# CH32F203RBT6-R1.net
KiCad netlist of a schematic drawn in Altium Designer
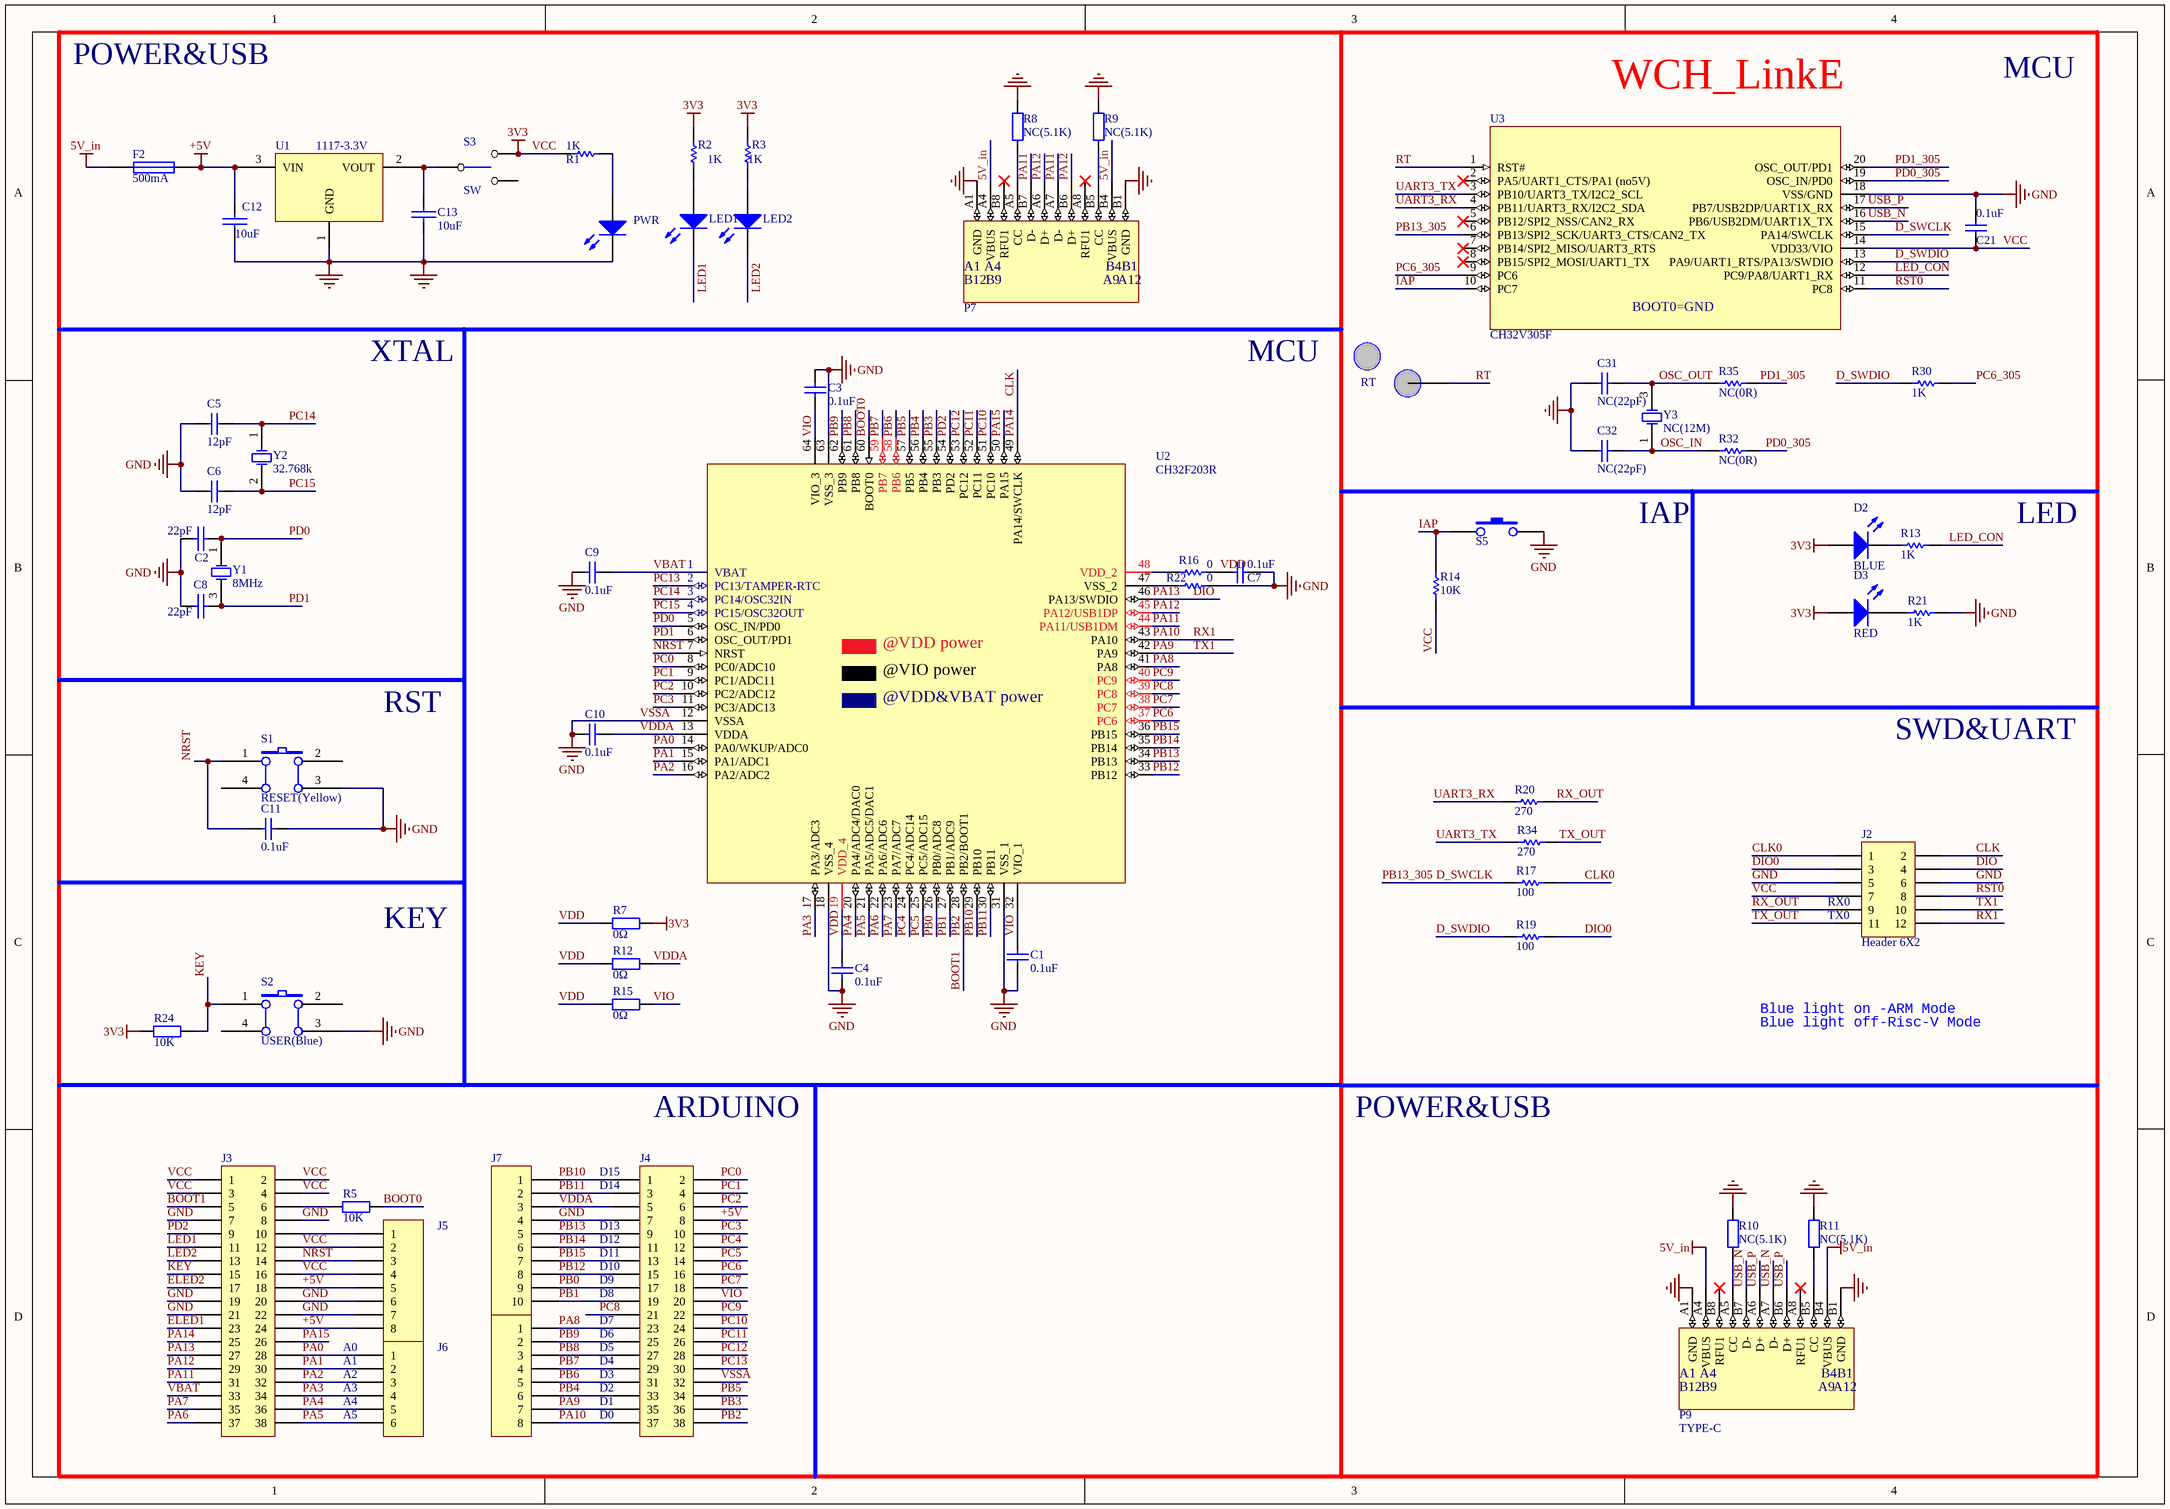
[diagram p0: CH32F203RBT6-R1.SchDoc]

(export (version "E")
  (design (tool "Eeschema 10.0.6"))
  (components
    (comp (ref "C1")
      (value "0.1uF")
      (footprint "0603_C")
      (description "Capacitor")
      (libsource (lib "Miscellaneous Devices") (part "Cap"))
    )
    (comp (ref "C2")
      (value "22pF")
      (footprint "0603_C")
      (description "Capacitor")
      (libsource (lib "*") (part "CAP"))
    )
    (comp (ref "C3")
      (value "0.1uF")
      (footprint "0603_C")
      (description "Capacitor")
      (libsource (lib "Miscellaneous Devices") (part "Cap"))
    )
    (comp (ref "C4")
      (value "0.1uF")
      (footprint "0603_C")
      (description "Capacitor")
      (libsource (lib "Miscellaneous Devices") (part "Cap"))
    )
    (comp (ref "C5")
      (value "12pF")
      (footprint "0603_C")
      (description "Capacitor")
      (libsource (lib "Miscellaneous Devices") (part "Cap"))
    )
    (comp (ref "C6")
      (value "12pF")
      (footprint "0603_C")
      (description "Capacitor")
      (libsource (lib "Miscellaneous Devices") (part "Cap"))
    )
    (comp (ref "C7")
      (value "0.1uF")
      (footprint "0603_C")
      (description "Capacitor")
      (libsource (lib "Miscellaneous Devices") (part "Cap"))
    )
    (comp (ref "C8")
      (value "22pF")
      (footprint "0603_C")
      (description "Capacitor")
      (libsource (lib "*") (part "CAP"))
    )
    (comp (ref "C9")
      (value "0.1uF")
      (footprint "0603_C")
      (description "Capacitor")
      (libsource (lib "Miscellaneous Devices") (part "Cap"))
    )
    (comp (ref "C10")
      (value "0.1uF")
      (footprint "0603_C")
      (description "Capacitor")
      (libsource (lib "Miscellaneous Devices") (part "Cap"))
    )
    (comp (ref "C11")
      (value "0.1uF")
      (footprint "0603_C")
      (description "Capacitor")
      (libsource (lib "Miscellaneous Devices") (part "Cap"))
    )
    (comp (ref "C12")
      (value "10uF")
      (footprint "3216_C")
      (description "Capacitor")
      (libsource (lib "*") (part "CAP"))
    )
    (comp (ref "C13")
      (value "10uF")
      (footprint "3216_C")
      (description "Capacitor")
      (libsource (lib "*") (part "CAP"))
    )
    (comp (ref "C21")
      (value "0.1uF")
      (footprint "0603_C")
      (description "Capacitor")
      (libsource (lib "Miscellaneous Devices") (part "Cap"))
    )
    (comp (ref "C31")
      (value "NC(22pF)")
      (footprint "0603_C")
      (description "Capacitor")
      (fields (field (name "PUBLISHER") "Altium Limited"))
      (libsource (lib "*") (part "Cap"))
    )
    (comp (ref "C32")
      (value "NC(22pF)")
      (footprint "0603_C")
      (description "Capacitor")
      (fields (field (name "PUBLISHER") "Altium Limited"))
      (libsource (lib "*") (part "Cap"))
    )
    (comp (ref "D2")
      (value "BLUE")
      (footprint "0603+")
      (description "Typical RED, GREEN, YELLOW, AMBER GaAs LED")
      (fields (field (name "PUBLISHER") "Altium Limited"))
      (libsource (lib "MYLIB") (part "D0603"))
    )
    (comp (ref "D3")
      (value "RED")
      (footprint "0603+")
      (description "Typical RED, GREEN, YELLOW, AMBER GaAs LED")
      (fields (field (name "PUBLISHER") "Altium Limited"))
      (libsource (lib "MYLIB") (part "D0603"))
    )
    (comp (ref "F2")
      (value "500mA")
      (footprint "0805")
      (description "Fuse")
      (libsource (lib "*") (part "FUSE1"))
    )
    (comp (ref "J2")
      (value "Header 6X2")
      (footprint "IDC12-2.54mm")
      (description "Header, 6-Pin, Dual row")
      (fields (field (name "PUBLISHER") "Altium Limited"))
      (libsource (lib "Miscellaneous Connectors") (part "Header 6X2"))
    )
    (comp (ref "J3")
      (value "Header 19X2")
      (footprint "IDC38-2.54mm")
      (description "Header, 19-Pin, Dual row")
      (fields (field (name "PUBLISHER") "Altium Limited"))
      (libsource (lib "Miscellaneous Connectors") (part "Header 19X2"))
    )
    (comp (ref "J4")
      (value "Header 19X2")
      (footprint "IDC38-2.54mm")
      (description "Header, 19-Pin, Dual row")
      (fields (field (name "PUBLISHER") "Altium Limited"))
      (libsource (lib "Miscellaneous Connectors") (part "Header 19X2"))
    )
    (comp (ref "J5")
      (value "Header 8")
      (footprint "SIP8-2.54mm")
      (description "Header, 8-Pin")
      (fields (field (name "PUBLISHER") "Altium Limited"))
      (libsource (lib "Miscellaneous Connectors") (part "Header 8"))
    )
    (comp (ref "J6")
      (value "Header 6")
      (footprint "SIP6-2.54MM")
      (description "Header, 6-Pin")
      (fields (field (name "PUBLISHER") "Altium Limited"))
      (libsource (lib "Miscellaneous Connectors") (part "Header 6"))
    )
    (comp (ref "J7")
      (value "Header 10")
      (footprint "SIP10-2.54mm")
      (description "Header, 10-Pin")
      (fields (field (name "PUBLISHER") "Altium Limited"))
      (libsource (lib "Miscellaneous Connectors") (part "Header 10"))
    )
    (comp (ref "J8")
      (value "Header 8")
      (footprint "SIP8-2.54mm")
      (description "Header, 8-Pin")
      (fields (field (name "PUBLISHER") "Altium Limited"))
      (libsource (lib "") (part "Header 8_1"))
    )
    (comp (ref "LED1")
      (value "LED1   blue")
      (footprint "0603+")
      (description "Typical INFRARED GaAs LED")
      (fields (field (name "PUBLISHER") "Altium Limited"))
      (libsource (lib "Miscellaneous Devices") (part "LED0"))
    )
    (comp (ref "LED2")
      (value "LED2  blue")
      (footprint "0603+")
      (description "Typical INFRARED GaAs LED")
      (fields (field (name "PUBLISHER") "Altium Limited"))
      (libsource (lib "Miscellaneous Devices") (part "LED0"))
    )
    (comp (ref "P7")
      (value "TYPE-C")
      (footprint "TYPE-C-Receptacle-2.0")
      (libsource (lib "*") (part "TYPE-C1"))
    )
    (comp (ref "P9")
      (value "TYPE-C")
      (footprint "TYPE-C-Receptacle-2.0")
      (libsource (lib "*") (part "TYPE-C1"))
    )
    (comp (ref "PWR")
      (value "POWER  red")
      (footprint "0603+")
      (description "Typical INFRARED GaAs LED")
      (fields (field (name "PUBLISHER") "Altium Limited"))
      (libsource (lib "Miscellaneous Devices") (part "LED0"))
    )
    (comp (ref "R1")
      (value "1K")
      (footprint "0603")
      (description "Semiconductor Resistor")
      (libsource (lib "Miscellaneous Devices") (part "Res Semi"))
    )
    (comp (ref "R2")
      (value "1K")
      (footprint "0603")
      (description "Semiconductor Resistor")
      (libsource (lib "Miscellaneous Devices") (part "Res Semi"))
    )
    (comp (ref "R3")
      (value "1K")
      (footprint "0603")
      (description "Semiconductor Resistor")
      (libsource (lib "Miscellaneous Devices") (part "Res Semi"))
    )
    (comp (ref "R5")
      (value "10K")
      (footprint "0603")
      (description "Resistor")
      (libsource (lib "") (part "Res2_2"))
    )
    (comp (ref "R7")
      (value "0Ω")
      (footprint "0603")
      (description "Resistor")
      (libsource (lib "Miscellaneous Devices") (part "Res2"))
    )
    (comp (ref "R8")
      (value "NC(5.1K)")
      (footprint "0603")
      (description "Resistor")
      (libsource (lib "") (part "Res2_1"))
    )
    (comp (ref "R9")
      (value "NC(5.1K)")
      (footprint "0603")
      (description "Resistor")
      (libsource (lib "") (part "Res2_1"))
    )
    (comp (ref "R10")
      (value "NC(5.1K)")
      (footprint "0603")
      (description "Resistor")
      (libsource (lib "") (part "Res2_3"))
    )
    (comp (ref "R11")
      (value "NC(5.1K)")
      (footprint "0603")
      (description "Resistor")
      (libsource (lib "") (part "Res2_3"))
    )
    (comp (ref "R12")
      (value "0Ω")
      (footprint "0603")
      (description "Resistor")
      (libsource (lib "Miscellaneous Devices") (part "Res2"))
    )
    (comp (ref "R13")
      (value "1K")
      (footprint "0603")
      (description "Resistor")
      (fields (field (name "PUBLISHER") "Altium Limited"))
      (libsource (lib "MYLIB") (part "0603-1"))
    )
    (comp (ref "R14")
      (value "10K")
      (footprint "0603")
      (description "Resistor")
      (fields (field (name "PUBLISHER") "Altium Limited"))
      (libsource (lib "MYLIB") (part "0603-1"))
    )
    (comp (ref "R15")
      (value "0Ω")
      (footprint "0603")
      (description "Resistor")
      (libsource (lib "Miscellaneous Devices") (part "Res2"))
    )
    (comp (ref "R16")
      (value "0")
      (footprint "0603")
      (description "Resistor")
      (fields (field (name "PUBLISHER") "Altium Limited"))
      (libsource (lib "MYLIB") (part "0603-1"))
    )
    (comp (ref "R17")
      (value "100")
      (footprint "0603")
      (description "Resistor")
      (fields (field (name "PUBLISHER") "Altium Limited"))
      (libsource (lib "MYLIB") (part "0603-1"))
    )
    (comp (ref "R19")
      (value "100")
      (footprint "0603")
      (description "Resistor")
      (fields (field (name "PUBLISHER") "Altium Limited"))
      (libsource (lib "MYLIB") (part "0603-1"))
    )
    (comp (ref "R20")
      (value "270")
      (footprint "0603")
      (description "Resistor")
      (fields (field (name "PUBLISHER") "Altium Limited"))
      (libsource (lib "MYLIB") (part "0603-1"))
    )
    (comp (ref "R21")
      (value "1K")
      (footprint "0603")
      (description "Resistor")
      (fields (field (name "PUBLISHER") "Altium Limited"))
      (libsource (lib "MYLIB") (part "0603-1"))
    )
    (comp (ref "R22")
      (value "0")
      (footprint "0603")
      (description "Resistor")
      (fields (field (name "PUBLISHER") "Altium Limited"))
      (libsource (lib "MYLIB") (part "0603-1"))
    )
    (comp (ref "R24")
      (value "10K")
      (footprint "0603")
      (description "Resistor")
      (libsource (lib "Miscellaneous Devices") (part "Res2"))
    )
    (comp (ref "R30")
      (value "1K")
      (footprint "0603")
      (description "Resistor")
      (fields (field (name "PUBLISHER") "Altium Limited"))
      (libsource (lib "MYLIB") (part "0603-1"))
    )
    (comp (ref "R32")
      (value "NC(0R)")
      (footprint "0603")
      (description "Resistor")
      (fields (field (name "PUBLISHER") "Altium Limited"))
      (libsource (lib "MYLIB") (part "0603-1"))
    )
    (comp (ref "R34")
      (value "270")
      (footprint "0603")
      (description "Resistor")
      (fields (field (name "PUBLISHER") "Altium Limited"))
      (libsource (lib "MYLIB") (part "0603-1"))
    )
    (comp (ref "R35")
      (value "NC(0R)")
      (footprint "0603")
      (description "Resistor")
      (fields (field (name "PUBLISHER") "Altium Limited"))
      (libsource (lib "MYLIB") (part "0603-1"))
    )
    (comp (ref "RT")
      (value "Testpoint")
      (footprint "TESTPOINT1")
      (description "测试点")
      (libsource (lib "wch_sch_others") (part "Testpoint"))
    )
    (comp (ref "S1")
      (value "RESET(Yellow)")
      (footprint "KEYX")
      (description "SE PUSHBUTTON")
      (libsource (lib "Documents") (part "SW PUSHBUTTON"))
    )
    (comp (ref "S2")
      (value "USER(Blue)")
      (footprint "KEYX")
      (description "SE PUSHBUTTON")
      (libsource (lib "Documents") (part "SW PUSHBUTTON"))
    )
    (comp (ref "S3") (value "SW") (footprint "SW1") (libsource (lib "MYSCH") (part "SW")))
    (comp (ref "S5") (value "KEY") (footprint "贴片按键") (libsource (lib "*") (part "KEY")))
    (comp (ref "U1")
      (value "1117-3.3V")
      (footprint "SOT-223")
      (libsource (lib "wch_sch_others") (part "1117-3.3V"))
    )
    (comp (ref "U2")
      (value "CH32F203R")
      (footprint "LQFP64M_10x10")
      (description "ARM M3 HD-MCU, 144MHz, 8*UART, 10*Timer, 4*OPA")
      (libsource (lib "CHXXX") (part "CH32F203R"))
    )
    (comp (ref "U3")
      (value "CH32V305F")
      (footprint "TSSOP20")
      (description "RISC-V FPU HD-MCU, 144MHz, USB_480M, CAN, UART*2, SPI")
      (libsource (lib "CHXXX") (part "CH32V305F"))
    )
    (comp (ref "Y1")
      (value "8MHz")
      (footprint "XT3225")
      (description "Crystal Oscillator")
      (fields (field (name "PUBLISHER") "Altium Limited"))
      (libsource (lib "*") (part "XTAL"))
    )
    (comp (ref "Y2")
      (value "32.768k")
      (footprint "FC-135")
      (description "Crystal Oscillator")
      (fields (field (name "PUBLISHER") "Altium Limited"))
      (libsource (lib "Miscellaneous Devices") (part "XTAL"))
    )
    (comp (ref "Y3")
      (value "NC(12M)")
      (footprint "XT3225")
      (description "Crystal Oscillator")
      (libsource (lib "*") (part "XTAL"))
    )
  )
  (nets
    (net (code "1") (name "+5V") (class "Default")
      (node (ref "C12") (pin "1") (pinfunction "1_1") (pintype "passive"))
      (node (ref "F2") (pin "2") (pinfunction "2_2") (pintype "passive"))
      (node (ref "J3") (pin "18") (pinfunction "18_18") (pintype "passive"))
      (node (ref "J3") (pin "24") (pinfunction "24_24") (pintype "passive"))
      (node (ref "J4") (pin "8") (pinfunction "8_8") (pintype "passive"))
      (node (ref "J5") (pin "5") (pinfunction "5_5") (pintype "passive"))
      (node (ref "J5") (pin "8") (pinfunction "8_8") (pintype "passive"))
      (node (ref "U1") (pin "3") (pinfunction "VIN_3") (pintype "passive"))
    )
    (net (code "2") (name "/BOOT0") (class "Default")
      (node (ref "R5") (pin "2") (pinfunction "2_2") (pintype "passive"))
      (node (ref "U2") (pin "60") (pinfunction "BOOT0_60") (pintype "input"))
    )
    (net (code "3") (name "/BOOT1") (class "Default")
      (node (ref "J3") (pin "5") (pinfunction "5_5") (pintype "passive"))
      (node (ref "J4") (pin "38") (pinfunction "38_38") (pintype "passive"))
      (node (ref "U2") (pin "28") (pinfunction "PB2/BOOT1_28") (pintype "bidirectional"))
    )
    (net (code "4") (name "/CLK") (class "Default")
      (node (ref "J2") (pin "2") (pinfunction "2_2") (pintype "passive"))
      (node (ref "J3") (pin "25") (pinfunction "25_25") (pintype "passive"))
      (node (ref "U2") (pin "49") (pinfunction "PA14/SWCLK_49") (pintype "bidirectional"))
    )
    (net (code "5") (name "/CLK0") (class "Default")
      (node (ref "J2") (pin "1") (pinfunction "1_1") (pintype "passive"))
      (node (ref "R17") (pin "1") (pinfunction "1_1") (pintype "passive"))
    )
    (net (code "6") (name "/DIO") (class "Default")
      (node (ref "J2") (pin "4") (pinfunction "4_4") (pintype "passive"))
      (node (ref "J3") (pin "27") (pinfunction "27_27") (pintype "passive"))
      (node (ref "U2") (pin "46") (pinfunction "PA13/SWDIO_46") (pintype "bidirectional"))
    )
    (net (code "7") (name "/DIO0") (class "Default")
      (node (ref "J2") (pin "3") (pinfunction "3_3") (pintype "passive"))
      (node (ref "R19") (pin "1") (pinfunction "1_1") (pintype "passive"))
    )
    (net (code "8") (name "/D_SWCLK") (class "Default")
      (node (ref "R17") (pin "2") (pinfunction "2_2") (pintype "passive"))
      (node (ref "U3") (pin "15") (pinfunction "PA14/SWCLK_15") (pintype "bidirectional"))
      (node (ref "U3") (pin "6") (pinfunction "PB13/SPI2_SCK/UART3_CTS/CAN2_TX_6") (pintype "bidirectional"))
    )
    (net (code "9") (name "/D_SWDIO") (class "Default")
      (node (ref "R19") (pin "2") (pinfunction "2_2") (pintype "passive"))
      (node (ref "R30") (pin "1") (pinfunction "1_1") (pintype "passive"))
      (node (ref "U3") (pin "13") (pinfunction "PA9/UART1_RTS/PA13/SWDIO_13") (pintype "bidirectional"))
    )
    (net (code "10") (name "/ELED1") (class "Default")
      (node (ref "J3") (pin "23") (pinfunction "23_23") (pintype "passive"))
    )
    (net (code "11") (name "/ELED2") (class "Default")
      (node (ref "J3") (pin "17") (pinfunction "17_17") (pintype "passive"))
    )
    (net (code "12") (name "/IAP") (class "Default")
      (node (ref "R14") (pin "1") (pinfunction "1_1") (pintype "passive"))
      (node (ref "S5") (pin "1") (pinfunction "1_1") (pintype "passive"))
      (node (ref "U3") (pin "10") (pinfunction "PC7_10") (pintype "bidirectional"))
    )
    (net (code "13") (name "/KEY") (class "Default")
      (node (ref "J3") (pin "15") (pinfunction "15_15") (pintype "passive"))
      (node (ref "R24") (pin "1") (pinfunction "1_1") (pintype "passive"))
      (node (ref "S2") (pin "1") (pinfunction "A0_1") (pintype "passive"))
    )
    (net (code "14") (name "/LED1") (class "Default")
      (node (ref "J3") (pin "11") (pinfunction "11_11") (pintype "passive"))
      (node (ref "LED1") (pin "2") (pinfunction "K_2") (pintype "passive"))
    )
    (net (code "15") (name "/LED2") (class "Default")
      (node (ref "J3") (pin "13") (pinfunction "13_13") (pintype "passive"))
      (node (ref "LED2") (pin "2") (pinfunction "K_2") (pintype "passive"))
    )
    (net (code "16") (name "/LED_CON") (class "Default")
      (node (ref "R13") (pin "1") (pinfunction "1_1") (pintype "passive"))
      (node (ref "U3") (pin "12") (pinfunction "PC9/PA8/UART1_RX_12") (pintype "bidirectional"))
    )
    (net (code "17") (name "/NRST") (class "Default")
      (node (ref "C11") (pin "2") (pinfunction "2_2") (pintype "passive"))
      (node (ref "J3") (pin "14") (pinfunction "14_14") (pintype "passive"))
      (node (ref "J5") (pin "3") (pinfunction "3_3") (pintype "passive"))
      (node (ref "S1") (pin "1") (pinfunction "A0_1") (pintype "passive"))
      (node (ref "U2") (pin "7") (pinfunction "NRST_7") (pintype "input"))
    )
    (net (code "18") (name "/OSC_IN") (class "Default")
      (node (ref "C32") (pin "2") (pinfunction "2_2") (pintype "passive"))
      (node (ref "R32") (pin "2") (pinfunction "2_2") (pintype "passive"))
      (node (ref "Y3") (pin "1") (pinfunction "OSC1_1") (pintype "passive"))
    )
    (net (code "19") (name "/OSC_OUT") (class "Default")
      (node (ref "C31") (pin "2") (pinfunction "2_2") (pintype "passive"))
      (node (ref "R35") (pin "2") (pinfunction "2_2") (pintype "passive"))
      (node (ref "Y3") (pin "3") (pinfunction "OSC2_3") (pintype "passive"))
    )
    (net (code "20") (name "/PA0") (class "Default")
      (node (ref "J3") (pin "28") (pinfunction "28_28") (pintype "passive"))
      (node (ref "J6") (pin "1") (pinfunction "1_1") (pintype "passive"))
      (node (ref "U2") (pin "14") (pinfunction "PA0/WKUP/ADC0_14") (pintype "bidirectional"))
    )
    (net (code "21") (name "/PA1") (class "Default")
      (node (ref "J3") (pin "30") (pinfunction "30_30") (pintype "passive"))
      (node (ref "J6") (pin "2") (pinfunction "2_2") (pintype "passive"))
      (node (ref "U2") (pin "15") (pinfunction "PA1/ADC1_15") (pintype "bidirectional"))
    )
    (net (code "22") (name "/PA2") (class "Default")
      (node (ref "J3") (pin "32") (pinfunction "32_32") (pintype "passive"))
      (node (ref "J6") (pin "3") (pinfunction "3_3") (pintype "passive"))
      (node (ref "U2") (pin "16") (pinfunction "PA2/ADC2_16") (pintype "bidirectional"))
    )
    (net (code "23") (name "/PA3") (class "Default")
      (node (ref "J3") (pin "34") (pinfunction "34_34") (pintype "passive"))
      (node (ref "J6") (pin "4") (pinfunction "4_4") (pintype "passive"))
      (node (ref "U2") (pin "17") (pinfunction "PA3/ADC3_17") (pintype "bidirectional"))
    )
    (net (code "24") (name "/PA4") (class "Default")
      (node (ref "J3") (pin "36") (pinfunction "36_36") (pintype "passive"))
      (node (ref "J6") (pin "5") (pinfunction "5_5") (pintype "passive"))
      (node (ref "U2") (pin "20") (pinfunction "PA4/ADC4/DAC0_20") (pintype "bidirectional"))
    )
    (net (code "25") (name "/PA5") (class "Default")
      (node (ref "J3") (pin "38") (pinfunction "38_38") (pintype "passive"))
      (node (ref "J6") (pin "6") (pinfunction "6_6") (pintype "passive"))
      (node (ref "U2") (pin "21") (pinfunction "PA5/ADC5/DAC1_21") (pintype "bidirectional"))
    )
    (net (code "26") (name "/PA6") (class "Default")
      (node (ref "J3") (pin "37") (pinfunction "37_37") (pintype "passive"))
      (node (ref "U2") (pin "22") (pinfunction "PA6/ADC6_22") (pintype "bidirectional"))
    )
    (net (code "27") (name "/PA7") (class "Default")
      (node (ref "J3") (pin "35") (pinfunction "35_35") (pintype "passive"))
      (node (ref "U2") (pin "23") (pinfunction "PA7/ADC7_23") (pintype "bidirectional"))
    )
    (net (code "28") (name "/PA8") (class "Default")
      (node (ref "J4") (pin "23") (pinfunction "23_23") (pintype "passive"))
      (node (ref "J8") (pin "1") (pinfunction "1_1") (pintype "passive"))
      (node (ref "U2") (pin "41") (pinfunction "PA8_41") (pintype "bidirectional"))
    )
    (net (code "29") (name "/PA9") (class "Default")
      (node (ref "J2") (pin "10") (pinfunction "10_10") (pintype "passive"))
      (node (ref "J4") (pin "35") (pinfunction "35_35") (pintype "passive"))
      (node (ref "J8") (pin "7") (pinfunction "7_7") (pintype "passive"))
      (node (ref "U2") (pin "42") (pinfunction "PA9_42") (pintype "bidirectional"))
    )
    (net (code "30") (name "/PA10") (class "Default")
      (node (ref "J2") (pin "12") (pinfunction "12_12") (pintype "passive"))
      (node (ref "J4") (pin "37") (pinfunction "37_37") (pintype "passive"))
      (node (ref "J8") (pin "8") (pinfunction "8_8") (pintype "passive"))
      (node (ref "U2") (pin "43") (pinfunction "PA10_43") (pintype "bidirectional"))
    )
    (net (code "31") (name "/PA11") (class "Default")
      (node (ref "J3") (pin "31") (pinfunction "31_31") (pintype "passive"))
      (node (ref "P7") (pin "A7") (pinfunction "D-_A7") (pintype "bidirectional"))
      (node (ref "P7") (pin "B7") (pinfunction "D-_B7") (pintype "bidirectional"))
      (node (ref "U2") (pin "44") (pinfunction "PA11/USB1DM_44") (pintype "bidirectional"))
    )
    (net (code "32") (name "/PA12") (class "Default")
      (node (ref "J3") (pin "29") (pinfunction "29_29") (pintype "passive"))
      (node (ref "P7") (pin "A6") (pinfunction "D+_A6") (pintype "bidirectional"))
      (node (ref "P7") (pin "B6") (pinfunction "D+_B6") (pintype "bidirectional"))
      (node (ref "U2") (pin "45") (pinfunction "PA12/USB1DP_45") (pintype "bidirectional"))
    )
    (net (code "33") (name "/PA15") (class "Default")
      (node (ref "J3") (pin "26") (pinfunction "26_26") (pintype "passive"))
      (node (ref "U2") (pin "50") (pinfunction "PA15_50") (pintype "bidirectional"))
    )
    (net (code "34") (name "/PB0") (class "Default")
      (node (ref "J4") (pin "17") (pinfunction "17_17") (pintype "passive"))
      (node (ref "J7") (pin "9") (pinfunction "9_9") (pintype "passive"))
      (node (ref "U2") (pin "26") (pinfunction "PB0/ADC8_26") (pintype "bidirectional"))
    )
    (net (code "35") (name "/PB1") (class "Default")
      (node (ref "J4") (pin "19") (pinfunction "19_19") (pintype "passive"))
      (node (ref "J7") (pin "10") (pinfunction "10_10") (pintype "passive"))
      (node (ref "U2") (pin "27") (pinfunction "PB1/ADC9_27") (pintype "bidirectional"))
    )
    (net (code "36") (name "/PB3") (class "Default")
      (node (ref "J4") (pin "36") (pinfunction "36_36") (pintype "passive"))
      (node (ref "U2") (pin "55") (pinfunction "PB3_55") (pintype "bidirectional"))
    )
    (net (code "37") (name "/PB4") (class "Default")
      (node (ref "J4") (pin "33") (pinfunction "33_33") (pintype "passive"))
      (node (ref "J8") (pin "6") (pinfunction "6_6") (pintype "passive"))
      (node (ref "U2") (pin "56") (pinfunction "PB4_56") (pintype "bidirectional"))
    )
    (net (code "38") (name "/PB5") (class "Default")
      (node (ref "J4") (pin "34") (pinfunction "34_34") (pintype "passive"))
      (node (ref "U2") (pin "57") (pinfunction "PB5_57") (pintype "bidirectional"))
    )
    (net (code "39") (name "/PB6") (class "Default")
      (node (ref "J4") (pin "31") (pinfunction "31_31") (pintype "passive"))
      (node (ref "J8") (pin "5") (pinfunction "5_5") (pintype "passive"))
      (node (ref "U2") (pin "58") (pinfunction "PB6_58") (pintype "bidirectional"))
    )
    (net (code "40") (name "/PB7") (class "Default")
      (node (ref "J4") (pin "29") (pinfunction "29_29") (pintype "passive"))
      (node (ref "J8") (pin "4") (pinfunction "4_4") (pintype "passive"))
      (node (ref "U2") (pin "59") (pinfunction "PB7_59") (pintype "bidirectional"))
    )
    (net (code "41") (name "/PB8") (class "Default")
      (node (ref "J4") (pin "27") (pinfunction "27_27") (pintype "passive"))
      (node (ref "J8") (pin "3") (pinfunction "3_3") (pintype "passive"))
      (node (ref "U2") (pin "61") (pinfunction "PB8_61") (pintype "bidirectional"))
    )
    (net (code "42") (name "/PB9") (class "Default")
      (node (ref "J4") (pin "25") (pinfunction "25_25") (pintype "passive"))
      (node (ref "J8") (pin "2") (pinfunction "2_2") (pintype "passive"))
      (node (ref "U2") (pin "62") (pinfunction "PB9_62") (pintype "bidirectional"))
    )
    (net (code "43") (name "/PB10") (class "Default")
      (node (ref "J4") (pin "1") (pinfunction "1_1") (pintype "passive"))
      (node (ref "J7") (pin "1") (pinfunction "1_1") (pintype "passive"))
      (node (ref "U2") (pin "29") (pinfunction "PB10_29") (pintype "bidirectional"))
    )
    (net (code "44") (name "/PB11") (class "Default")
      (node (ref "J4") (pin "3") (pinfunction "3_3") (pintype "passive"))
      (node (ref "J7") (pin "2") (pinfunction "2_2") (pintype "passive"))
      (node (ref "U2") (pin "30") (pinfunction "PB11_30") (pintype "bidirectional"))
    )
    (net (code "45") (name "/PB12") (class "Default")
      (node (ref "J4") (pin "15") (pinfunction "15_15") (pintype "passive"))
      (node (ref "J7") (pin "8") (pinfunction "8_8") (pintype "passive"))
      (node (ref "U2") (pin "33") (pinfunction "PB12_33") (pintype "bidirectional"))
    )
    (net (code "46") (name "/PB13") (class "Default")
      (node (ref "J4") (pin "9") (pinfunction "9_9") (pintype "passive"))
      (node (ref "J7") (pin "5") (pinfunction "5_5") (pintype "passive"))
      (node (ref "U2") (pin "34") (pinfunction "PB13_34") (pintype "bidirectional"))
    )
    (net (code "47") (name "/PB14") (class "Default")
      (node (ref "J4") (pin "11") (pinfunction "11_11") (pintype "passive"))
      (node (ref "J7") (pin "6") (pinfunction "6_6") (pintype "passive"))
      (node (ref "U2") (pin "35") (pinfunction "PB14_35") (pintype "bidirectional"))
    )
    (net (code "48") (name "/PB15") (class "Default")
      (node (ref "J4") (pin "13") (pinfunction "13_13") (pintype "passive"))
      (node (ref "J7") (pin "7") (pinfunction "7_7") (pintype "passive"))
      (node (ref "U2") (pin "36") (pinfunction "PB15_36") (pintype "bidirectional"))
    )
    (net (code "49") (name "/PC0") (class "Default")
      (node (ref "J4") (pin "2") (pinfunction "2_2") (pintype "passive"))
      (node (ref "U2") (pin "8") (pinfunction "PC0/ADC10_8") (pintype "bidirectional"))
    )
    (net (code "50") (name "/PC1") (class "Default")
      (node (ref "J4") (pin "4") (pinfunction "4_4") (pintype "passive"))
      (node (ref "U2") (pin "9") (pinfunction "PC1/ADC11_9") (pintype "bidirectional"))
    )
    (net (code "51") (name "/PC2") (class "Default")
      (node (ref "J4") (pin "6") (pinfunction "6_6") (pintype "passive"))
      (node (ref "U2") (pin "10") (pinfunction "PC2/ADC12_10") (pintype "bidirectional"))
    )
    (net (code "52") (name "/PC3") (class "Default")
      (node (ref "J4") (pin "10") (pinfunction "10_10") (pintype "passive"))
      (node (ref "U2") (pin "11") (pinfunction "PC3/ADC13_11") (pintype "bidirectional"))
    )
    (net (code "53") (name "/PC4") (class "Default")
      (node (ref "J4") (pin "12") (pinfunction "12_12") (pintype "passive"))
      (node (ref "U2") (pin "24") (pinfunction "PC4/ADC14_24") (pintype "bidirectional"))
    )
    (net (code "54") (name "/PC5") (class "Default")
      (node (ref "J4") (pin "14") (pinfunction "14_14") (pintype "passive"))
      (node (ref "U2") (pin "25") (pinfunction "PC5/ADC15_25") (pintype "bidirectional"))
    )
    (net (code "55") (name "/PC6") (class "Default")
      (node (ref "J4") (pin "16") (pinfunction "16_16") (pintype "passive"))
      (node (ref "U2") (pin "37") (pinfunction "PC6_37") (pintype "bidirectional"))
    )
    (net (code "56") (name "/PC6_305") (class "Default")
      (node (ref "R30") (pin "2") (pinfunction "2_2") (pintype "passive"))
      (node (ref "U3") (pin "9") (pinfunction "PC6_9") (pintype "bidirectional"))
    )
    (net (code "57") (name "/PC7") (class "Default")
      (node (ref "J4") (pin "18") (pinfunction "18_18") (pintype "passive"))
      (node (ref "U2") (pin "38") (pinfunction "PC7_38") (pintype "bidirectional"))
    )
    (net (code "58") (name "/PC8") (class "Default")
      (node (ref "J4") (pin "21") (pinfunction "21_21") (pintype "passive"))
      (node (ref "U2") (pin "39") (pinfunction "PC8_39") (pintype "bidirectional"))
    )
    (net (code "59") (name "/PC9") (class "Default")
      (node (ref "J4") (pin "22") (pinfunction "22_22") (pintype "passive"))
      (node (ref "U2") (pin "40") (pinfunction "PC9_40") (pintype "bidirectional"))
    )
    (net (code "60") (name "/PC10") (class "Default")
      (node (ref "J4") (pin "24") (pinfunction "24_24") (pintype "passive"))
      (node (ref "U2") (pin "51") (pinfunction "PC10_51") (pintype "bidirectional"))
    )
    (net (code "61") (name "/PC11") (class "Default")
      (node (ref "J4") (pin "26") (pinfunction "26_26") (pintype "passive"))
      (node (ref "U2") (pin "52") (pinfunction "PC11_52") (pintype "bidirectional"))
    )
    (net (code "62") (name "/PC12") (class "Default")
      (node (ref "J4") (pin "28") (pinfunction "28_28") (pintype "passive"))
      (node (ref "U2") (pin "53") (pinfunction "PC12_53") (pintype "bidirectional"))
    )
    (net (code "63") (name "/PC13") (class "Default")
      (node (ref "J4") (pin "30") (pinfunction "30_30") (pintype "passive"))
      (node (ref "U2") (pin "2") (pinfunction "PC13/TAMPER-RTC_2") (pintype "bidirectional"))
    )
    (net (code "64") (name "/PC14") (class "Default")
      (node (ref "C5") (pin "1") (pinfunction "1_1") (pintype "passive"))
      (node (ref "U2") (pin "3") (pinfunction "PC14/OSC32IN_3") (pintype "bidirectional"))
      (node (ref "Y2") (pin "1") (pinfunction "OSC1_1") (pintype "passive"))
    )
    (net (code "65") (name "/PC15") (class "Default")
      (node (ref "C6") (pin "1") (pinfunction "1_1") (pintype "passive"))
      (node (ref "U2") (pin "4") (pinfunction "PC15/OSC32OUT_4") (pintype "bidirectional"))
      (node (ref "Y2") (pin "2") (pinfunction "OSC2_2") (pintype "passive"))
    )
    (net (code "66") (name "/PD0") (class "Default")
      (node (ref "C2") (pin "2") (pinfunction "2_2") (pintype "passive"))
      (node (ref "U2") (pin "5") (pinfunction "OSC_IN/PD0_5") (pintype "bidirectional"))
      (node (ref "Y1") (pin "1") (pinfunction "OSC1_1") (pintype "passive"))
    )
    (net (code "67") (name "/PD0_305") (class "Default")
      (node (ref "R32") (pin "1") (pinfunction "1_1") (pintype "passive"))
      (node (ref "U3") (pin "19") (pinfunction "OSC_IN/PD0_19") (pintype "bidirectional"))
    )
    (net (code "68") (name "/PD1") (class "Default")
      (node (ref "C8") (pin "2") (pinfunction "2_2") (pintype "passive"))
      (node (ref "U2") (pin "6") (pinfunction "OSC_OUT/PD1_6") (pintype "bidirectional"))
      (node (ref "Y1") (pin "3") (pinfunction "OSC2_3") (pintype "passive"))
    )
    (net (code "69") (name "/PD1_305") (class "Default")
      (node (ref "R35") (pin "1") (pinfunction "1_1") (pintype "passive"))
      (node (ref "U3") (pin "20") (pinfunction "OSC_OUT/PD1_20") (pintype "bidirectional"))
    )
    (net (code "70") (name "/PD2") (class "Default")
      (node (ref "J3") (pin "9") (pinfunction "9_9") (pintype "passive"))
      (node (ref "U2") (pin "54") (pinfunction "PD2_54") (pintype "bidirectional"))
    )
    (net (code "71") (name "/RST0") (class "Default")
      (node (ref "J2") (pin "8") (pinfunction "8_8") (pintype "passive"))
      (node (ref "U3") (pin "11") (pinfunction "PC8_11") (pintype "bidirectional"))
    )
    (net (code "72") (name "/RT") (class "Default")
      (node (ref "RT") (pin "1") (pinfunction "point_1") (pintype "passive"))
      (node (ref "U3") (pin "1") (pinfunction "RST#_1") (pintype "input"))
    )
    (net (code "73") (name "/RX_OUT") (class "Default")
      (node (ref "J2") (pin "9") (pinfunction "9_9") (pintype "passive"))
      (node (ref "R20") (pin "1") (pinfunction "1_1") (pintype "passive"))
    )
    (net (code "74") (name "/TX_OUT") (class "Default")
      (node (ref "J2") (pin "11") (pinfunction "11_11") (pintype "passive"))
      (node (ref "R34") (pin "1") (pinfunction "1_1") (pintype "passive"))
    )
    (net (code "75") (name "/UART3_RX") (class "Default")
      (node (ref "R20") (pin "2") (pinfunction "2_2") (pintype "passive"))
      (node (ref "U3") (pin "4") (pinfunction "PB11/UART3_RX/I2C2_SDA_4") (pintype "bidirectional"))
    )
    (net (code "76") (name "/UART3_TX") (class "Default")
      (node (ref "R34") (pin "2") (pinfunction "2_2") (pintype "passive"))
      (node (ref "U3") (pin "3") (pinfunction "PB10/UART3_TX/I2C2_SCL_3") (pintype "bidirectional"))
    )
    (net (code "77") (name "/USB_N") (class "Default")
      (node (ref "P9") (pin "A7") (pinfunction "D-_A7") (pintype "bidirectional"))
      (node (ref "P9") (pin "B7") (pinfunction "D-_B7") (pintype "bidirectional"))
      (node (ref "U3") (pin "16") (pinfunction "PB6/USB2DM/UART1X_TX_16") (pintype "bidirectional"))
    )
    (net (code "78") (name "/USB_P") (class "Default")
      (node (ref "P9") (pin "A6") (pinfunction "D+_A6") (pintype "bidirectional"))
      (node (ref "P9") (pin "B6") (pinfunction "D+_B6") (pintype "bidirectional"))
      (node (ref "U3") (pin "17") (pinfunction "PB7/USB2DP/UART1X_RX_17") (pintype "bidirectional"))
    )
    (net (code "79") (name "/VBAT") (class "Default")
      (node (ref "C9") (pin "1") (pinfunction "1_1") (pintype "passive"))
      (node (ref "J3") (pin "33") (pinfunction "33_33") (pintype "passive"))
      (node (ref "U2") (pin "1") (pinfunction "VBAT_1") (pintype "power_in"))
    )
    (net (code "80") (name "/VDD") (class "Default")
      (node (ref "C4") (pin "2") (pinfunction "2_2") (pintype "passive"))
      (node (ref "C7") (pin "2") (pinfunction "2_2") (pintype "passive"))
      (node (ref "R12") (pin "2") (pinfunction "2_2") (pintype "passive"))
      (node (ref "R15") (pin "2") (pinfunction "2_2") (pintype "passive"))
      (node (ref "R16") (pin "1") (pinfunction "1_1") (pintype "passive"))
      (node (ref "R7") (pin "2") (pinfunction "2_2") (pintype "passive"))
      (node (ref "U2") (pin "19") (pinfunction "VDD_4_19") (pintype "power_in"))
    )
    (net (code "81") (name "/VDDA") (class "Default")
      (node (ref "C10") (pin "1") (pinfunction "1_1") (pintype "passive"))
      (node (ref "J4") (pin "5") (pinfunction "5_5") (pintype "passive"))
      (node (ref "J7") (pin "3") (pinfunction "3_3") (pintype "passive"))
      (node (ref "R12") (pin "1") (pinfunction "1_1") (pintype "passive"))
      (node (ref "U2") (pin "13") (pinfunction "VDDA_13") (pintype "power_in"))
    )
    (net (code "82") (name "/VIO") (class "Default")
      (node (ref "C1") (pin "2") (pinfunction "2_2") (pintype "passive"))
      (node (ref "C3") (pin "2") (pinfunction "2_2") (pintype "passive"))
      (node (ref "J4") (pin "20") (pinfunction "20_20") (pintype "passive"))
      (node (ref "R15") (pin "1") (pinfunction "1_1") (pintype "passive"))
      (node (ref "U2") (pin "32") (pinfunction "VIO_1_32") (pintype "power_in"))
      (node (ref "U2") (pin "64") (pinfunction "VIO_3_64") (pintype "power_in"))
    )
    (net (code "83") (name "3V3") (class "Default")
      (node (ref "C21") (pin "1") (pinfunction "1_1") (pintype "passive"))
      (node (ref "D2") (pin "1") (pinfunction "A_1") (pintype "passive"))
      (node (ref "D3") (pin "1") (pinfunction "A_1") (pintype "passive"))
      (node (ref "J2") (pin "7") (pinfunction "7_7") (pintype "passive"))
      (node (ref "J3") (pin "1") (pinfunction "1_1") (pintype "passive"))
      (node (ref "J3") (pin "12") (pinfunction "12_12") (pintype "passive"))
      (node (ref "J3") (pin "16") (pinfunction "16_16") (pintype "passive"))
      (node (ref "J3") (pin "2") (pinfunction "2_2") (pintype "passive"))
      (node (ref "J3") (pin "3") (pinfunction "3_3") (pintype "passive"))
      (node (ref "J3") (pin "4") (pinfunction "4_4") (pintype "passive"))
      (node (ref "J5") (pin "2") (pinfunction "2_2") (pintype "passive"))
      (node (ref "J5") (pin "4") (pinfunction "4_4") (pintype "passive"))
      (node (ref "R1") (pin "2") (pinfunction "2_2") (pintype "passive"))
      (node (ref "R14") (pin "2") (pinfunction "2_2") (pintype "passive"))
      (node (ref "R2") (pin "1") (pinfunction "1_1") (pintype "passive"))
      (node (ref "R24") (pin "2") (pinfunction "2_2") (pintype "passive"))
      (node (ref "R3") (pin "1") (pinfunction "1_1") (pintype "passive"))
      (node (ref "R7") (pin "1") (pinfunction "1_1") (pintype "passive"))
      (node (ref "S3") (pin "3") (pinfunction "3_3") (pintype "passive"))
      (node (ref "U3") (pin "14") (pinfunction "VDD33/VIO_14") (pintype "power_in"))
    )
    (net (code "84") (name "5V_in") (class "Default")
      (node (ref "F2") (pin "1") (pinfunction "1_1") (pintype "passive"))
      (node (ref "P7") (pin "A4") (pinfunction "VBUS_A4") (pintype "bidirectional"))
      (node (ref "P7") (pin "B4") (pinfunction "VBUS_B4") (pintype "bidirectional"))
      (node (ref "P9") (pin "A4") (pinfunction "VBUS_A4") (pintype "bidirectional"))
      (node (ref "P9") (pin "B4") (pinfunction "VBUS_B4") (pintype "bidirectional"))
    )
    (net (code "85") (name "GND") (class "Default")
      (node (ref "C1") (pin "1") (pinfunction "1_1") (pintype "passive"))
      (node (ref "C10") (pin "2") (pinfunction "2_2") (pintype "passive"))
      (node (ref "C11") (pin "1") (pinfunction "1_1") (pintype "passive"))
      (node (ref "C12") (pin "2") (pinfunction "2_2") (pintype "passive"))
      (node (ref "C13") (pin "2") (pinfunction "2_2") (pintype "passive"))
      (node (ref "C2") (pin "1") (pinfunction "1_1") (pintype "passive"))
      (node (ref "C21") (pin "2") (pinfunction "2_2") (pintype "passive"))
      (node (ref "C3") (pin "1") (pinfunction "1_1") (pintype "passive"))
      (node (ref "C31") (pin "1") (pinfunction "1_1") (pintype "passive"))
      (node (ref "C32") (pin "1") (pinfunction "1_1") (pintype "passive"))
      (node (ref "C4") (pin "1") (pinfunction "1_1") (pintype "passive"))
      (node (ref "C5") (pin "2") (pinfunction "2_2") (pintype "passive"))
      (node (ref "C6") (pin "2") (pinfunction "2_2") (pintype "passive"))
      (node (ref "C7") (pin "1") (pinfunction "1_1") (pintype "passive"))
      (node (ref "C8") (pin "1") (pinfunction "1_1") (pintype "passive"))
      (node (ref "C9") (pin "2") (pinfunction "2_2") (pintype "passive"))
      (node (ref "J2") (pin "5") (pinfunction "5_5") (pintype "passive"))
      (node (ref "J2") (pin "6") (pinfunction "6_6") (pintype "passive"))
      (node (ref "J3") (pin "19") (pinfunction "19_19") (pintype "passive"))
      (node (ref "J3") (pin "20") (pinfunction "20_20") (pintype "passive"))
      (node (ref "J3") (pin "21") (pinfunction "21_21") (pintype "passive"))
      (node (ref "J3") (pin "22") (pinfunction "22_22") (pintype "passive"))
      (node (ref "J3") (pin "7") (pinfunction "7_7") (pintype "passive"))
      (node (ref "J3") (pin "8") (pinfunction "8_8") (pintype "passive"))
      (node (ref "J4") (pin "32") (pinfunction "32_32") (pintype "passive"))
      (node (ref "J4") (pin "7") (pinfunction "7_7") (pintype "passive"))
      (node (ref "J5") (pin "6") (pinfunction "6_6") (pintype "passive"))
      (node (ref "J5") (pin "7") (pinfunction "7_7") (pintype "passive"))
      (node (ref "J7") (pin "4") (pinfunction "4_4") (pintype "passive"))
      (node (ref "P7") (pin "A1") (pinfunction "GND_A1") (pintype "bidirectional"))
      (node (ref "P7") (pin "B1") (pinfunction "GND_B1") (pintype "bidirectional"))
      (node (ref "P9") (pin "A1") (pinfunction "GND_A1") (pintype "bidirectional"))
      (node (ref "P9") (pin "B1") (pinfunction "GND_B1") (pintype "bidirectional"))
      (node (ref "PWR") (pin "2") (pinfunction "K_2") (pintype "passive"))
      (node (ref "R10") (pin "2") (pinfunction "2_2") (pintype "passive"))
      (node (ref "R11") (pin "2") (pinfunction "2_2") (pintype "passive"))
      (node (ref "R21") (pin "1") (pinfunction "1_1") (pintype "passive"))
      (node (ref "R22") (pin "1") (pinfunction "1_1") (pintype "passive"))
      (node (ref "R8") (pin "1") (pinfunction "1_1") (pintype "passive"))
      (node (ref "R9") (pin "1") (pinfunction "1_1") (pintype "passive"))
      (node (ref "S1") (pin "3") (pinfunction "B1_3") (pintype "passive"))
      (node (ref "S2") (pin "3") (pinfunction "B1_3") (pintype "passive"))
      (node (ref "S5") (pin "2") (pinfunction "2_2") (pintype "passive"))
      (node (ref "U1") (pin "1") (pinfunction "GND_1") (pintype "passive"))
      (node (ref "U2") (pin "12") (pinfunction "VSSA_12") (pintype "power_in"))
      (node (ref "U2") (pin "18") (pinfunction "VSS_4_18") (pintype "power_in"))
      (node (ref "U2") (pin "31") (pinfunction "VSS_1_31") (pintype "power_in"))
      (node (ref "U2") (pin "63") (pinfunction "VSS_3_63") (pintype "power_in"))
      (node (ref "U3") (pin "18") (pinfunction "VSS/GND_18") (pintype "power_in"))
    )
    (net (code "86") (name "Net-(D2-K)") (class "Default")
      (node (ref "D2") (pin "2") (pinfunction "K_2") (pintype "passive"))
      (node (ref "R13") (pin "2") (pinfunction "2_2") (pintype "passive"))
    )
    (net (code "87") (name "Net-(D3-K)") (class "Default")
      (node (ref "D3") (pin "2") (pinfunction "K_2") (pintype "passive"))
      (node (ref "R21") (pin "2") (pinfunction "2_2") (pintype "passive"))
    )
    (net (code "88") (name "Net-(J3-Pad6)") (class "Default")
      (node (ref "J3") (pin "6") (pinfunction "6_6") (pintype "passive"))
      (node (ref "R5") (pin "1") (pinfunction "1_1") (pintype "passive"))
    )
    (net (code "89") (name "Net-(J3-Pad10)") (class "Default")
      (node (ref "J3") (pin "10") (pinfunction "10_10") (pintype "passive"))
      (node (ref "J5") (pin "1") (pinfunction "1_1") (pintype "passive"))
    )
    (net (code "90") (name "Net-(LED1-A)") (class "Default")
      (node (ref "LED1") (pin "1") (pinfunction "A_1") (pintype "passive"))
      (node (ref "R2") (pin "2") (pinfunction "2_2") (pintype "passive"))
    )
    (net (code "91") (name "Net-(LED2-A)") (class "Default")
      (node (ref "LED2") (pin "1") (pinfunction "A_1") (pintype "passive"))
      (node (ref "R3") (pin "2") (pinfunction "2_2") (pintype "passive"))
    )
    (net (code "92") (name "Net-(P7-CC-PadA5)") (class "Default")
      (node (ref "P7") (pin "A5") (pinfunction "CC_A5") (pintype "bidirectional"))
      (node (ref "R8") (pin "2") (pinfunction "2_2") (pintype "passive"))
    )
    (net (code "93") (name "Net-(P7-CC-PadB5)") (class "Default")
      (node (ref "P7") (pin "B5") (pinfunction "CC_B5") (pintype "bidirectional"))
      (node (ref "R9") (pin "2") (pinfunction "2_2") (pintype "passive"))
    )
    (net (code "94") (name "Net-(P9-CC-PadA5)") (class "Default")
      (node (ref "P9") (pin "A5") (pinfunction "CC_A5") (pintype "bidirectional"))
      (node (ref "R10") (pin "1") (pinfunction "1_1") (pintype "passive"))
    )
    (net (code "95") (name "Net-(P9-CC-PadB5)") (class "Default")
      (node (ref "P9") (pin "B5") (pinfunction "CC_B5") (pintype "bidirectional"))
      (node (ref "R11") (pin "1") (pinfunction "1_1") (pintype "passive"))
    )
    (net (code "96") (name "Net-(PWR-A)") (class "Default")
      (node (ref "PWR") (pin "1") (pinfunction "A_1") (pintype "passive"))
      (node (ref "R1") (pin "1") (pinfunction "1_1") (pintype "passive"))
    )
    (net (code "97") (name "Net-(U1-VOUT)") (class "Default")
      (node (ref "C13") (pin "1") (pinfunction "1_1") (pintype "passive"))
      (node (ref "S3") (pin "1") (pinfunction "1_1") (pintype "passive"))
      (node (ref "U1") (pin "2") (pinfunction "VOUT_2") (pintype "passive"))
    )
    (net (code "98") (name "Net-(U2-VDD_2)") (class "Default")
      (node (ref "R16") (pin "2") (pinfunction "2_2") (pintype "passive"))
      (node (ref "U2") (pin "48") (pinfunction "VDD_2_48") (pintype "power_in"))
    )
    (net (code "99") (name "Net-(U2-VSS_2)") (class "Default")
      (node (ref "R22") (pin "2") (pinfunction "2_2") (pintype "passive"))
      (node (ref "U2") (pin "47") (pinfunction "VSS_2_47") (pintype "power_in"))
    )
    (net (code "100") (name "unconnected-(P7-RFU1-PadA8)") (class "Default")
      (node (ref "P7") (pin "A8") (pinfunction "RFU1_A8") (pintype "bidirectional+no_connect"))
    )
    (net (code "101") (name "unconnected-(P7-RFU1-PadB8)") (class "Default")
      (node (ref "P7") (pin "B8") (pinfunction "RFU1_B8") (pintype "bidirectional+no_connect"))
    )
    (net (code "102") (name "unconnected-(P9-RFU1-PadA8)") (class "Default")
      (node (ref "P9") (pin "A8") (pinfunction "RFU1_A8") (pintype "bidirectional+no_connect"))
    )
    (net (code "103") (name "unconnected-(P9-RFU1-PadB8)") (class "Default")
      (node (ref "P9") (pin "B8") (pinfunction "RFU1_B8") (pintype "bidirectional+no_connect"))
    )
    (net (code "104") (name "unconnected-(S1-A1-Pad4)") (class "Default")
      (node (ref "S1") (pin "4") (pinfunction "A1_4") (pintype "passive"))
    )
    (net (code "105") (name "unconnected-(S1-B0-Pad2)") (class "Default")
      (node (ref "S1") (pin "2") (pinfunction "B0_2") (pintype "passive"))
    )
    (net (code "106") (name "unconnected-(S2-A1-Pad4)") (class "Default")
      (node (ref "S2") (pin "4") (pinfunction "A1_4") (pintype "passive"))
    )
    (net (code "107") (name "unconnected-(S2-B0-Pad2)") (class "Default")
      (node (ref "S2") (pin "2") (pinfunction "B0_2") (pintype "passive"))
    )
    (net (code "108") (name "unconnected-(S3-Pad2)") (class "Default")
      (node (ref "S3") (pin "2") (pinfunction "2_2") (pintype "passive"))
    )
    (net (code "109") (name "unconnected-(U3-PA5{slash}UART1_CTS{slash}PA1_(no5V)-Pad2)") (class "Default")
      (node (ref "U3") (pin "2") (pinfunction "PA5/UART1_CTS/PA1_(no5V)_2") (pintype "bidirectional+no_connect"))
    )
    (net (code "110") (name "unconnected-(U3-PB12{slash}SPI2_NSS{slash}CAN2_RX-Pad5)") (class "Default")
      (node (ref "U3") (pin "5") (pinfunction "PB12/SPI2_NSS/CAN2_RX_5") (pintype "bidirectional+no_connect"))
    )
    (net (code "111") (name "unconnected-(U3-PB14{slash}SPI2_MISO{slash}UART3_RTS-Pad7)") (class "Default")
      (node (ref "U3") (pin "7") (pinfunction "PB14/SPI2_MISO/UART3_RTS_7") (pintype "bidirectional+no_connect"))
    )
    (net (code "112") (name "unconnected-(U3-PB15{slash}SPI2_MOSI{slash}UART1_TX-Pad8)") (class "Default")
      (node (ref "U3") (pin "8") (pinfunction "PB15/SPI2_MOSI/UART1_TX_8") (pintype "bidirectional+no_connect"))
    )
  )
)
